# MainBoard_KONZEVIC.net
KiCad netlist of a schematic drawn in Altium Designer
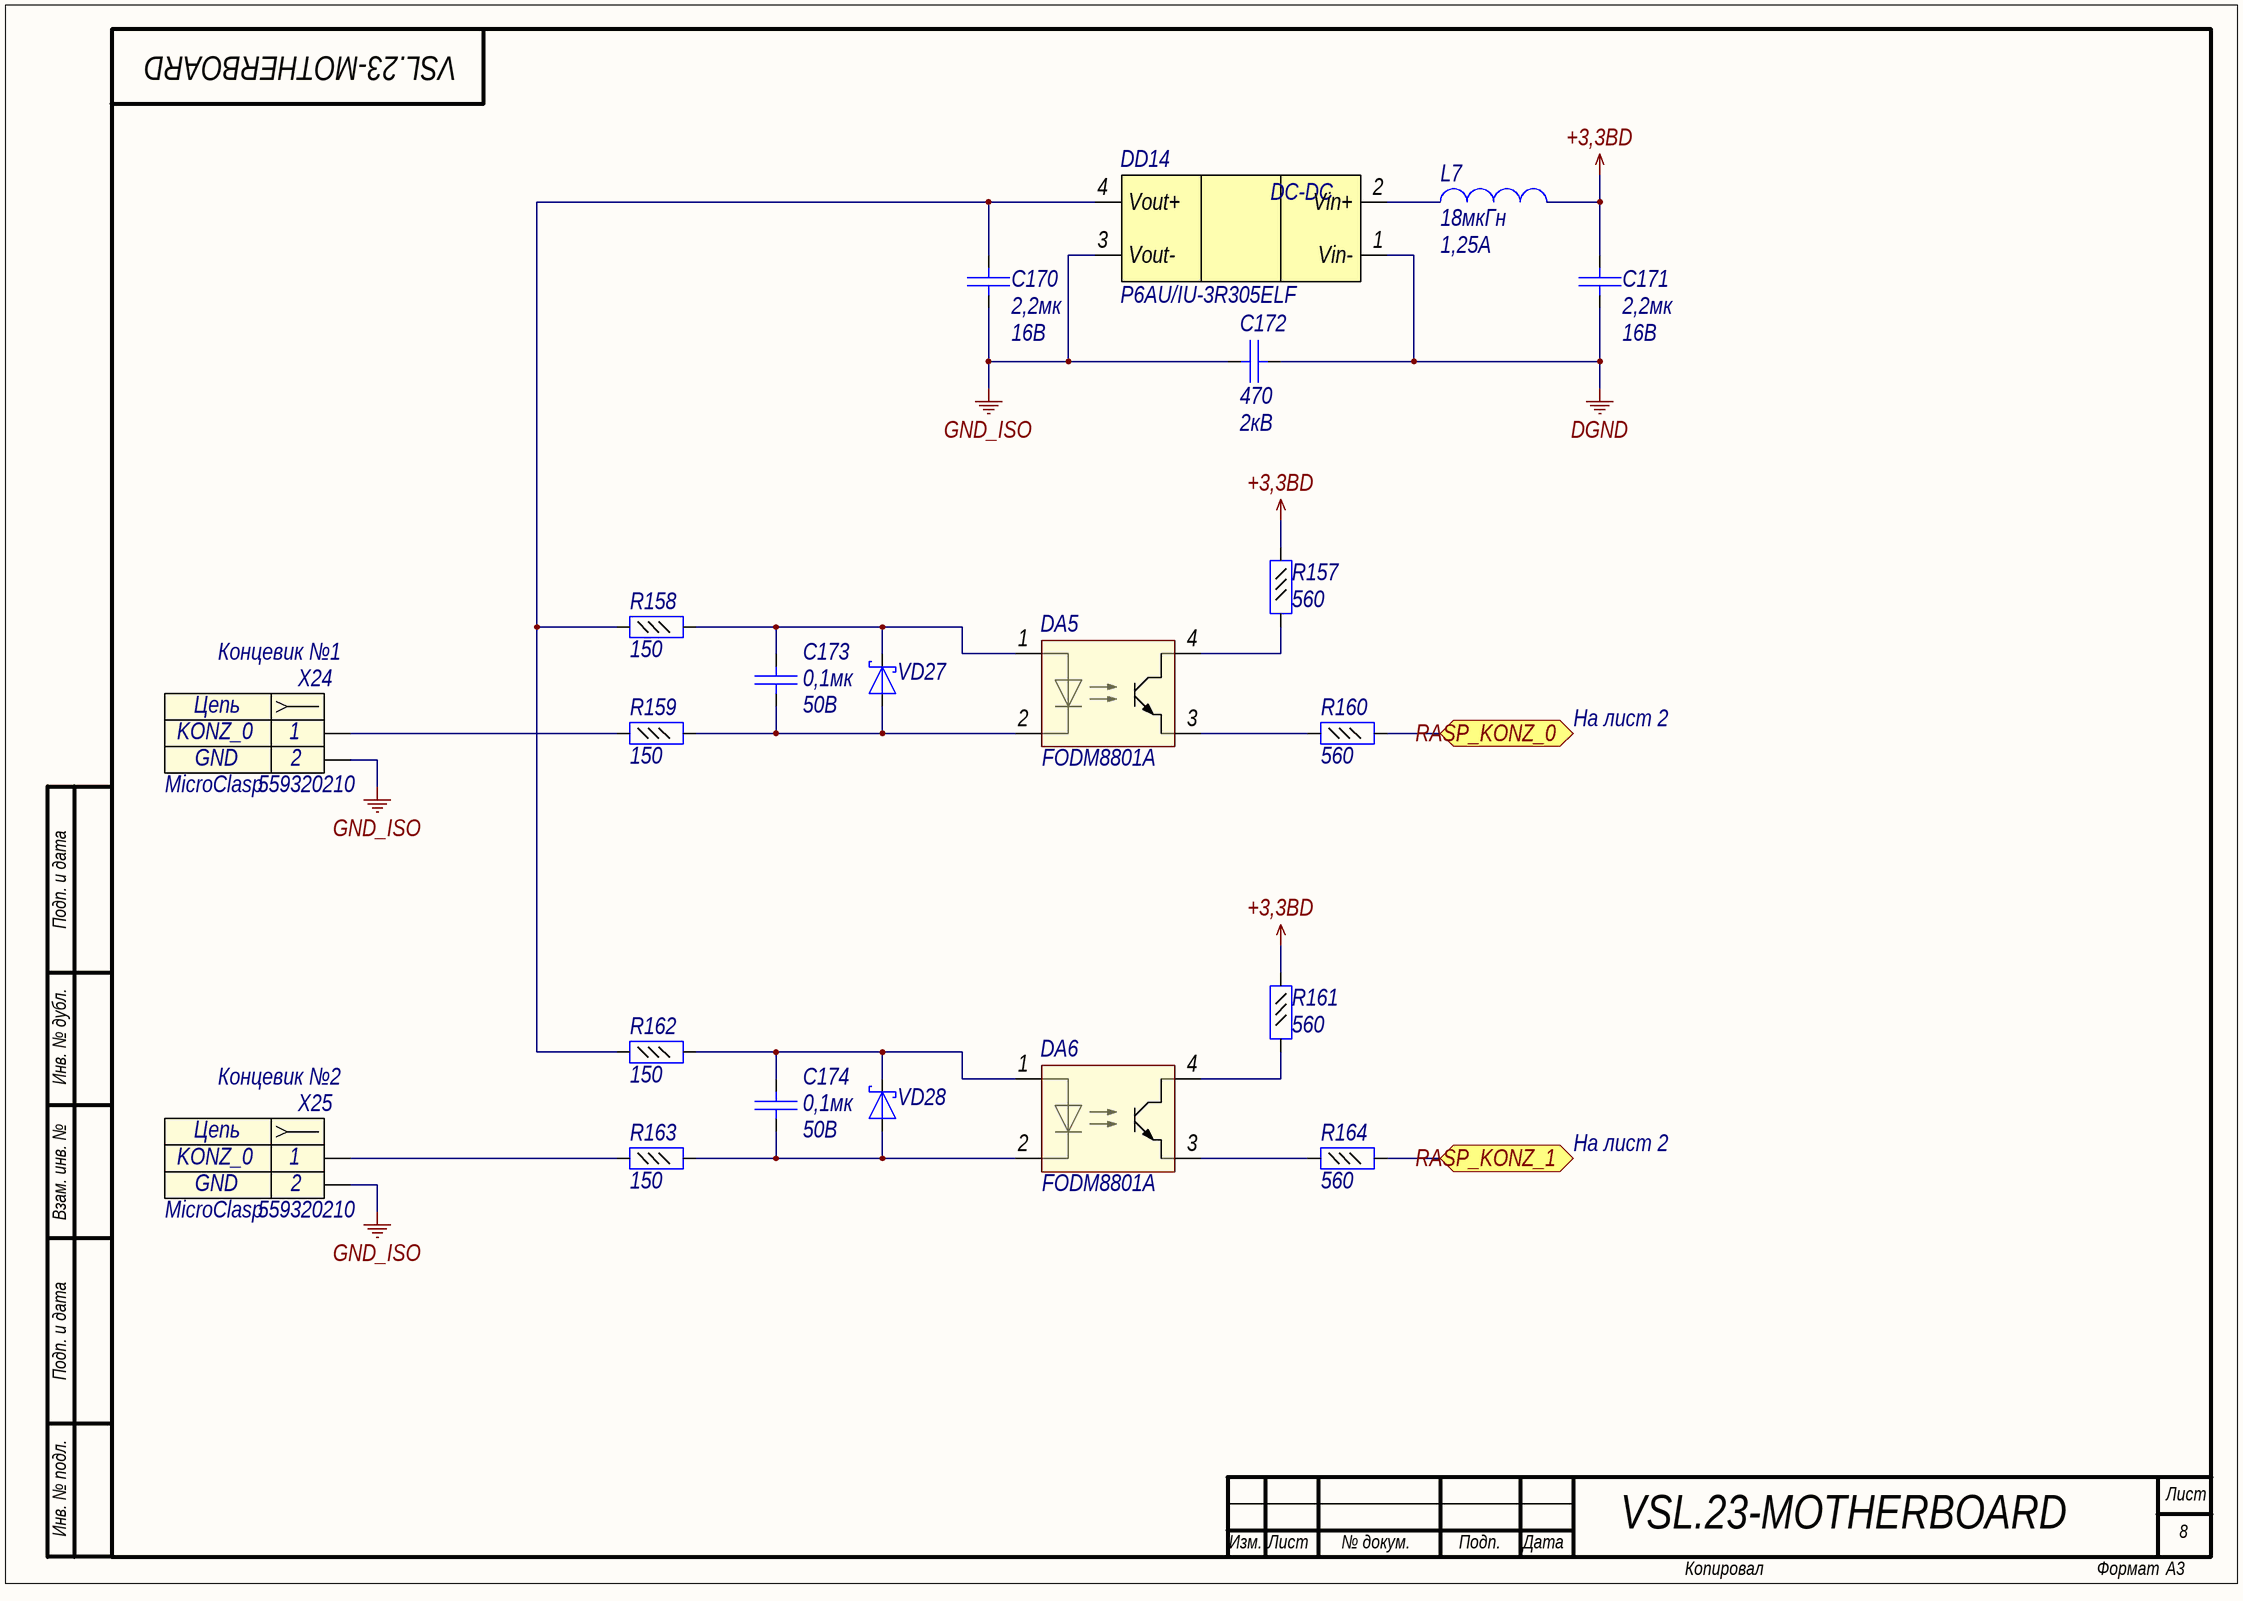
[diagram p0: MainBoard_KONZEVIC.SchDoc]

(export (version "E")
  (design (tool "Eeschema 10.0.6"))
  (components
    (comp (ref "C170")
      (value "2,2мк")
      (footprint "C0603")
      (description "Конденсатор")
      (fields (field (name "VOLTAGE") "16B") (field (name "PART NUMBER") "GRM188Z71C225ME43J"))
      (libsource (lib "MOP44") (part "Capacitor"))
    )
    (comp (ref "C171")
      (value "2,2мк")
      (footprint "C0603")
      (description "Конденсатор")
      (fields (field (name "VOLTAGE") "16B") (field (name "PART NUMBER") "GRM188Z71C225ME43J"))
      (libsource (lib "MOP44") (part "Capacitor"))
    )
    (comp (ref "C172")
      (value "470")
      (footprint "C1206")
      (description "Конденсатор")
      (fields
        (field (name "VOLTAGE") "2кВ")
        (field (name "PART NUMBER") "CC1206KKX7RDBB471 ")
        (field (name "Comment") "Capacitor")
      )
      (libsource (lib "MOP44") (part "Capacitor"))
    )
    (comp (ref "C173")
      (value "0,1мк")
      (footprint "C0402")
      (description "Конденсатор")
      (fields
        (field (name "VOLTAGE") "50В")
        (field (name "PART NUMBER") "GRM155R71H104KE14D ")
        (field (name "Comment") "Capacitor")
      )
      (libsource (lib "MOP44") (part "Capacitor"))
    )
    (comp (ref "C174")
      (value "0,1мк")
      (footprint "C0402")
      (description "Конденсатор")
      (fields
        (field (name "VOLTAGE") "50В")
        (field (name "PART NUMBER") "GRM155R71H104KE14D ")
        (field (name "Comment") "Capacitor")
      )
      (libsource (lib "MOP44") (part "Capacitor"))
    )
    (comp (ref "DA5")
      (value "OPTO-1")
      (footprint "Miniflat4")
      (description "Опторазвязка")
      (fields (field (name "PART NUMBER") "FODM8801A") (field (name "MANUFACTURER") "ON Semiconductor"))
      (libsource (lib "MOP44") (part "OPTO-1"))
    )
    (comp (ref "DA6")
      (value "OPTO-1")
      (footprint "Miniflat4")
      (description "Опторазвязка")
      (fields (field (name "PART NUMBER") "FODM8801A") (field (name "MANUFACTURER") "ON Semiconductor"))
      (libsource (lib "MOP44") (part "OPTO-1"))
    )
    (comp (ref "DD14")
      (value "P6AU-xxxxELF")
      (footprint "SIP4")
      (description "DC/DC преобразователь")
      (fields
        (field (name "PART NUMBER") "P6AU/IU-3R305ELF")
        (field (name "MANUFACTURER") "PEAK Electronics")
      )
      (libsource (lib "MOP44") (part "P6AU-xxxxELF"))
    )
    (comp (ref "L7")
      (value "18мкГн")
      (footprint "SDR0604")
      (description "EMI Suppression Filter")
      (fields
        (field (name "RATED CURRENT") "1,25A")
        (field (name "PART NUMBER") "SDR0604- 180YL")
        (field (name "Comment") "Inductor")
      )
      (libsource (lib "MOP44") (part "Inductor"))
    )
    (comp (ref "R157")
      (value "560")
      (footprint "R0402")
      (description "Резистор")
      (fields (field (name "PART NUMBER") "RC0402FR-07560RL") (field (name "POWER") "0,062Вт"))
      (libsource (lib "") (part "Resistor_0,062Вт_1"))
    )
    (comp (ref "R158")
      (value "150")
      (footprint "R0402")
      (description "Резистор")
      (fields (field (name "PART NUMBER") "RC0402FR-07150RL") (field (name "POWER") "0,062Вт"))
      (libsource (lib "MOP44") (part "Resistor_0,062Вт"))
    )
    (comp (ref "R159")
      (value "150")
      (footprint "R0402")
      (description "Резистор")
      (fields (field (name "PART NUMBER") "RC0402FR-07150RL") (field (name "POWER") "0,062Вт"))
      (libsource (lib "MOP44") (part "Resistor_0,062Вт"))
    )
    (comp (ref "R160")
      (value "560")
      (footprint "R0402")
      (description "Резистор")
      (fields (field (name "PART NUMBER") "RC0402FR-07560RL") (field (name "POWER") "0,062Вт"))
      (libsource (lib "MOP44") (part "Resistor_0,062Вт"))
    )
    (comp (ref "R161")
      (value "560")
      (footprint "R0402")
      (description "Резистор")
      (fields (field (name "PART NUMBER") "RC0402FR-07560RL") (field (name "POWER") "0,062Вт"))
      (libsource (lib "") (part "Resistor_0,062Вт_1"))
    )
    (comp (ref "R162")
      (value "150")
      (footprint "R0402")
      (description "Резистор")
      (fields (field (name "PART NUMBER") "RC0402FR-07150RL") (field (name "POWER") "0,062Вт"))
      (libsource (lib "MOP44") (part "Resistor_0,062Вт"))
    )
    (comp (ref "R163")
      (value "150")
      (footprint "R0402")
      (description "Резистор")
      (fields (field (name "PART NUMBER") "RC0402FR-07150RL") (field (name "POWER") "0,062Вт"))
      (libsource (lib "MOP44") (part "Resistor_0,062Вт"))
    )
    (comp (ref "R164")
      (value "560")
      (footprint "R0402")
      (description "Резистор")
      (fields (field (name "PART NUMBER") "RC0402FR-07560RL") (field (name "POWER") "0,062Вт"))
      (libsource (lib "MOP44") (part "Resistor_0,062Вт"))
    )
    (comp (ref "VD27")
      (value "DiodeSchottky")
      (footprint "SOD-123")
      (description "Диод Шоттки")
      (fields (field (name "PART NUMBER") "MBR2H100SFT3G"))
      (libsource (lib "MOP44") (part "DiodeSchottky"))
    )
    (comp (ref "VD28")
      (value "DiodeSchottky")
      (footprint "SOD-123")
      (description "Диод Шоттки")
      (fields (field (name "PART NUMBER") "MBR2H100SFT3G"))
      (libsource (lib "MOP44") (part "DiodeSchottky"))
    )
    (comp (ref "X24")
      (value "Концевик №1")
      (footprint "MOLEX_559320210")
      (description "Разъем - 2 конт. розетка")
      (fields (field (name "PART NAME") "MicroClasp") (field (name "PART NUMBER") "559320210"))
      (libsource (lib "MOP44") (part "Header_2_sct"))
    )
    (comp (ref "X25")
      (value "Концевик №2")
      (footprint "MOLEX_559320210")
      (description "Разъем - 2 конт. розетка")
      (fields (field (name "PART NAME") "MicroClasp") (field (name "PART NUMBER") "559320210"))
      (libsource (lib "MOP44") (part "Header_2_sct"))
    )
  )
  (nets
    (net (code "1") (name "+3,3BD") (class "Default")
      (node (ref "C171") (pin "2") (pinfunction "2_2") (pintype "passive"))
      (node (ref "L7") (pin "1") (pinfunction "1_1") (pintype "passive"))
      (node (ref "R157") (pin "1") (pinfunction "1_1") (pintype "passive"))
      (node (ref "R161") (pin "1") (pinfunction "1_1") (pintype "passive"))
    )
    (net (code "2") (name "/RASP_KONZ_0") (class "Default")
      (node (ref "R160") (pin "2") (pinfunction "2_2") (pintype "passive"))
    )
    (net (code "3") (name "/RASP_KONZ_1") (class "Default")
      (node (ref "R164") (pin "2") (pinfunction "2_2") (pintype "passive"))
    )
    (net (code "4") (name "DGND") (class "Default")
      (node (ref "C171") (pin "1") (pinfunction "1_1") (pintype "passive"))
      (node (ref "C172") (pin "1") (pinfunction "1_1") (pintype "passive"))
      (node (ref "DD14") (pin "1") (pinfunction "Vin-_1") (pintype "passive"))
    )
    (net (code "5") (name "GND_ISO") (class "Default")
      (node (ref "C170") (pin "1") (pinfunction "1_1") (pintype "passive"))
      (node (ref "C172") (pin "2") (pinfunction "2_2") (pintype "passive"))
      (node (ref "DD14") (pin "3") (pinfunction "Vout-_3") (pintype "passive"))
      (node (ref "X24") (pin "2") (pinfunction "2_2") (pintype "passive"))
      (node (ref "X25") (pin "2") (pinfunction "2_2") (pintype "passive"))
    )
    (net (code "6") (name "Net-(DA5-Pad3)") (class "Default")
      (node (ref "DA5") (pin "3") (pintype "passive"))
      (node (ref "R160") (pin "1") (pinfunction "1_1") (pintype "passive"))
    )
    (net (code "7") (name "Net-(DA5-Pad4)") (class "Default")
      (node (ref "DA5") (pin "4") (pintype "passive"))
      (node (ref "R157") (pin "2") (pinfunction "2_2") (pintype "passive"))
    )
    (net (code "8") (name "Net-(DA6-Pad3)") (class "Default")
      (node (ref "DA6") (pin "3") (pintype "passive"))
      (node (ref "R164") (pin "1") (pinfunction "1_1") (pintype "passive"))
    )
    (net (code "9") (name "Net-(DA6-Pad4)") (class "Default")
      (node (ref "DA6") (pin "4") (pintype "passive"))
      (node (ref "R161") (pin "2") (pinfunction "2_2") (pintype "passive"))
    )
    (net (code "10") (name "Net-(DD14-Vin+)") (class "Default")
      (node (ref "DD14") (pin "2") (pinfunction "Vin+_2") (pintype "passive"))
      (node (ref "L7") (pin "2") (pinfunction "2_2") (pintype "passive"))
    )
    (net (code "11") (name "Net-(DD14-Vout+)") (class "Default")
      (node (ref "C170") (pin "2") (pinfunction "2_2") (pintype "passive"))
      (node (ref "DD14") (pin "4") (pinfunction "Vout+_4") (pintype "passive"))
      (node (ref "R158") (pin "1") (pinfunction "1_1") (pintype "passive"))
      (node (ref "R162") (pin "1") (pinfunction "1_1") (pintype "passive"))
    )
    (net (code "12") (name "Net-(R159-Pad1)") (class "Default")
      (node (ref "R159") (pin "1") (pinfunction "1_1") (pintype "passive"))
      (node (ref "X24") (pin "1") (pinfunction "1_1") (pintype "passive"))
    )
    (net (code "13") (name "Net-(R163-Pad1)") (class "Default")
      (node (ref "R163") (pin "1") (pinfunction "1_1") (pintype "passive"))
      (node (ref "X25") (pin "1") (pinfunction "1_1") (pintype "passive"))
    )
    (net (code "14") (name "Net-(VD27-A)") (class "Default")
      (node (ref "C173") (pin "1") (pinfunction "1_1") (pintype "passive"))
      (node (ref "DA5") (pin "2") (pintype "passive"))
      (node (ref "R159") (pin "2") (pinfunction "2_2") (pintype "passive"))
      (node (ref "VD27") (pin "2") (pinfunction "A_2") (pintype "passive"))
    )
    (net (code "15") (name "Net-(VD27-K)") (class "Default")
      (node (ref "C173") (pin "2") (pinfunction "2_2") (pintype "passive"))
      (node (ref "DA5") (pin "1") (pintype "passive"))
      (node (ref "R158") (pin "2") (pinfunction "2_2") (pintype "passive"))
      (node (ref "VD27") (pin "1") (pinfunction "K_1") (pintype "passive"))
    )
    (net (code "16") (name "Net-(VD28-A)") (class "Default")
      (node (ref "C174") (pin "1") (pinfunction "1_1") (pintype "passive"))
      (node (ref "DA6") (pin "2") (pintype "passive"))
      (node (ref "R163") (pin "2") (pinfunction "2_2") (pintype "passive"))
      (node (ref "VD28") (pin "2") (pinfunction "A_2") (pintype "passive"))
    )
    (net (code "17") (name "Net-(VD28-K)") (class "Default")
      (node (ref "C174") (pin "2") (pinfunction "2_2") (pintype "passive"))
      (node (ref "DA6") (pin "1") (pintype "passive"))
      (node (ref "R162") (pin "2") (pinfunction "2_2") (pintype "passive"))
      (node (ref "VD28") (pin "1") (pinfunction "K_1") (pintype "passive"))
    )
  )
)
